# Ruido.net
KiCad netlist of a schematic drawn in Altium Designer
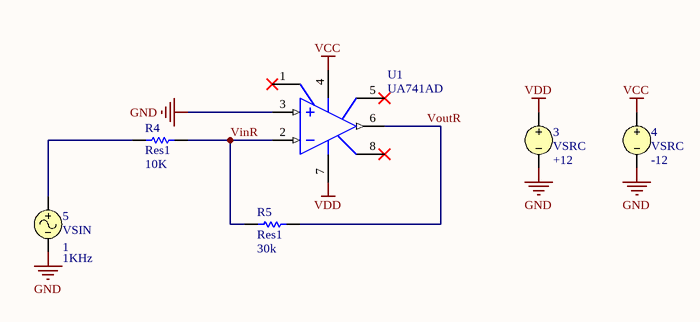
[diagram p0: Ruido.SchDoc]

(export (version "E")
  (design (tool "Eeschema 10.0.6"))
  (components
    (comp (ref "3")
      (value "VSRC")
      (description "Voltage Source")
      (fields (field (name "ALTIUM_VALUE") "+12") (field (name "PUBLISHER") "Altium Limited"))
      (libsource (lib "Simulation Sources") (part "VSRC"))
    )
    (comp (ref "4")
      (value "VSRC")
      (description "Voltage Source")
      (fields (field (name "ALTIUM_VALUE") "-12") (field (name "PUBLISHER") "Altium Limited"))
      (libsource (lib "Simulation Sources") (part "VSRC"))
    )
    (comp (ref "5")
      (value "VSIN")
      (description "Sinusoidal Voltage Source")
      (fields
        (field (name "AMPLITUDE") "1")
        (field (name "FREQUENCY") "1KHz")
        (field (name "PUBLISHER") "Altium Limited")
      )
      (libsource (lib "Simulation Sources") (part "VSIN"))
    )
    (comp (ref "R4")
      (value "Res1")
      (footprint "AXIAL-0.3")
      (description "Resistor")
      (fields (field (name "ALTIUM_VALUE") "10K") (field (name "PUBLISHER") "Altium Limited"))
      (libsource (lib "Miscellaneous Devices") (part "Res1"))
    )
    (comp (ref "R5")
      (value "Res1")
      (footprint "AXIAL-0.3")
      (description "Resistor")
      (fields (field (name "ALTIUM_VALUE") "30k") (field (name "PUBLISHER") "Altium Limited"))
      (libsource (lib "Miscellaneous Devices") (part "Res1"))
    )
    (comp (ref "U1")
      (value "UA741AD")
      (footprint "SO8_L")
      (description "General-Purpose Single Operational Amplifier")
      (fields (field (name "PUBLISHER") "Altium Limited"))
      (libsource (lib "ST Operational Amplifier") (part "UA741AD"))
    )
  )
  (nets
    (net (code "1") (name "/VinR") (class "Default")
      (node (ref "R4") (pin "2") (pinfunction "2_2") (pintype "passive"))
      (node (ref "R5") (pin "1") (pinfunction "1_1") (pintype "passive"))
      (node (ref "U1") (pin "2") (pinfunction "IN-_2") (pintype "input"))
    )
    (net (code "2") (name "/VoutR") (class "Default")
      (node (ref "R5") (pin "2") (pinfunction "2_2") (pintype "passive"))
      (node (ref "U1") (pin "6") (pinfunction "OUT_6") (pintype "output"))
    )
    (net (code "3") (name "GND") (class "Default")
      (node (ref "3") (pin "2") (pinfunction "2_2") (pintype "passive"))
      (node (ref "4") (pin "2") (pinfunction "2_2") (pintype "passive"))
      (node (ref "5") (pin "2") (pinfunction "2_2") (pintype "passive"))
      (node (ref "U1") (pin "3") (pinfunction "IN+_3") (pintype "input"))
    )
    (net (code "4") (name "Net-(5-Pad1)") (class "Default")
      (node (ref "5") (pin "1") (pinfunction "1_1") (pintype "passive"))
      (node (ref "R4") (pin "1") (pinfunction "1_1") (pintype "passive"))
    )
    (net (code "5") (name "VCC") (class "Default")
      (node (ref "4") (pin "1") (pinfunction "1_1") (pintype "passive"))
      (node (ref "U1") (pin "4") (pinfunction "V-_4") (pintype "power_in"))
    )
    (net (code "6") (name "VDD") (class "Default")
      (node (ref "3") (pin "1") (pinfunction "1_1") (pintype "passive"))
      (node (ref "U1") (pin "7") (pinfunction "V+_7") (pintype "power_in"))
    )
    (net (code "7") (name "unconnected-(U1-NC-Pad8)") (class "Default")
      (node (ref "U1") (pin "8") (pinfunction "NC_8") (pintype "passive+no_connect"))
    )
    (net (code "8") (name "unconnected-(U1-OS_NULL-Pad1)") (class "Default")
      (node (ref "U1") (pin "1") (pinfunction "OS_NULL_1") (pintype "passive+no_connect"))
    )
    (net (code "9") (name "unconnected-(U1-OS_NULL-Pad5)") (class "Default")
      (node (ref "U1") (pin "5") (pinfunction "OS_NULL_5") (pintype "passive+no_connect"))
    )
  )
)
